# SimpleC64-128Cart-Dual.net
KiCad netlist of a schematic drawn in EAGLE
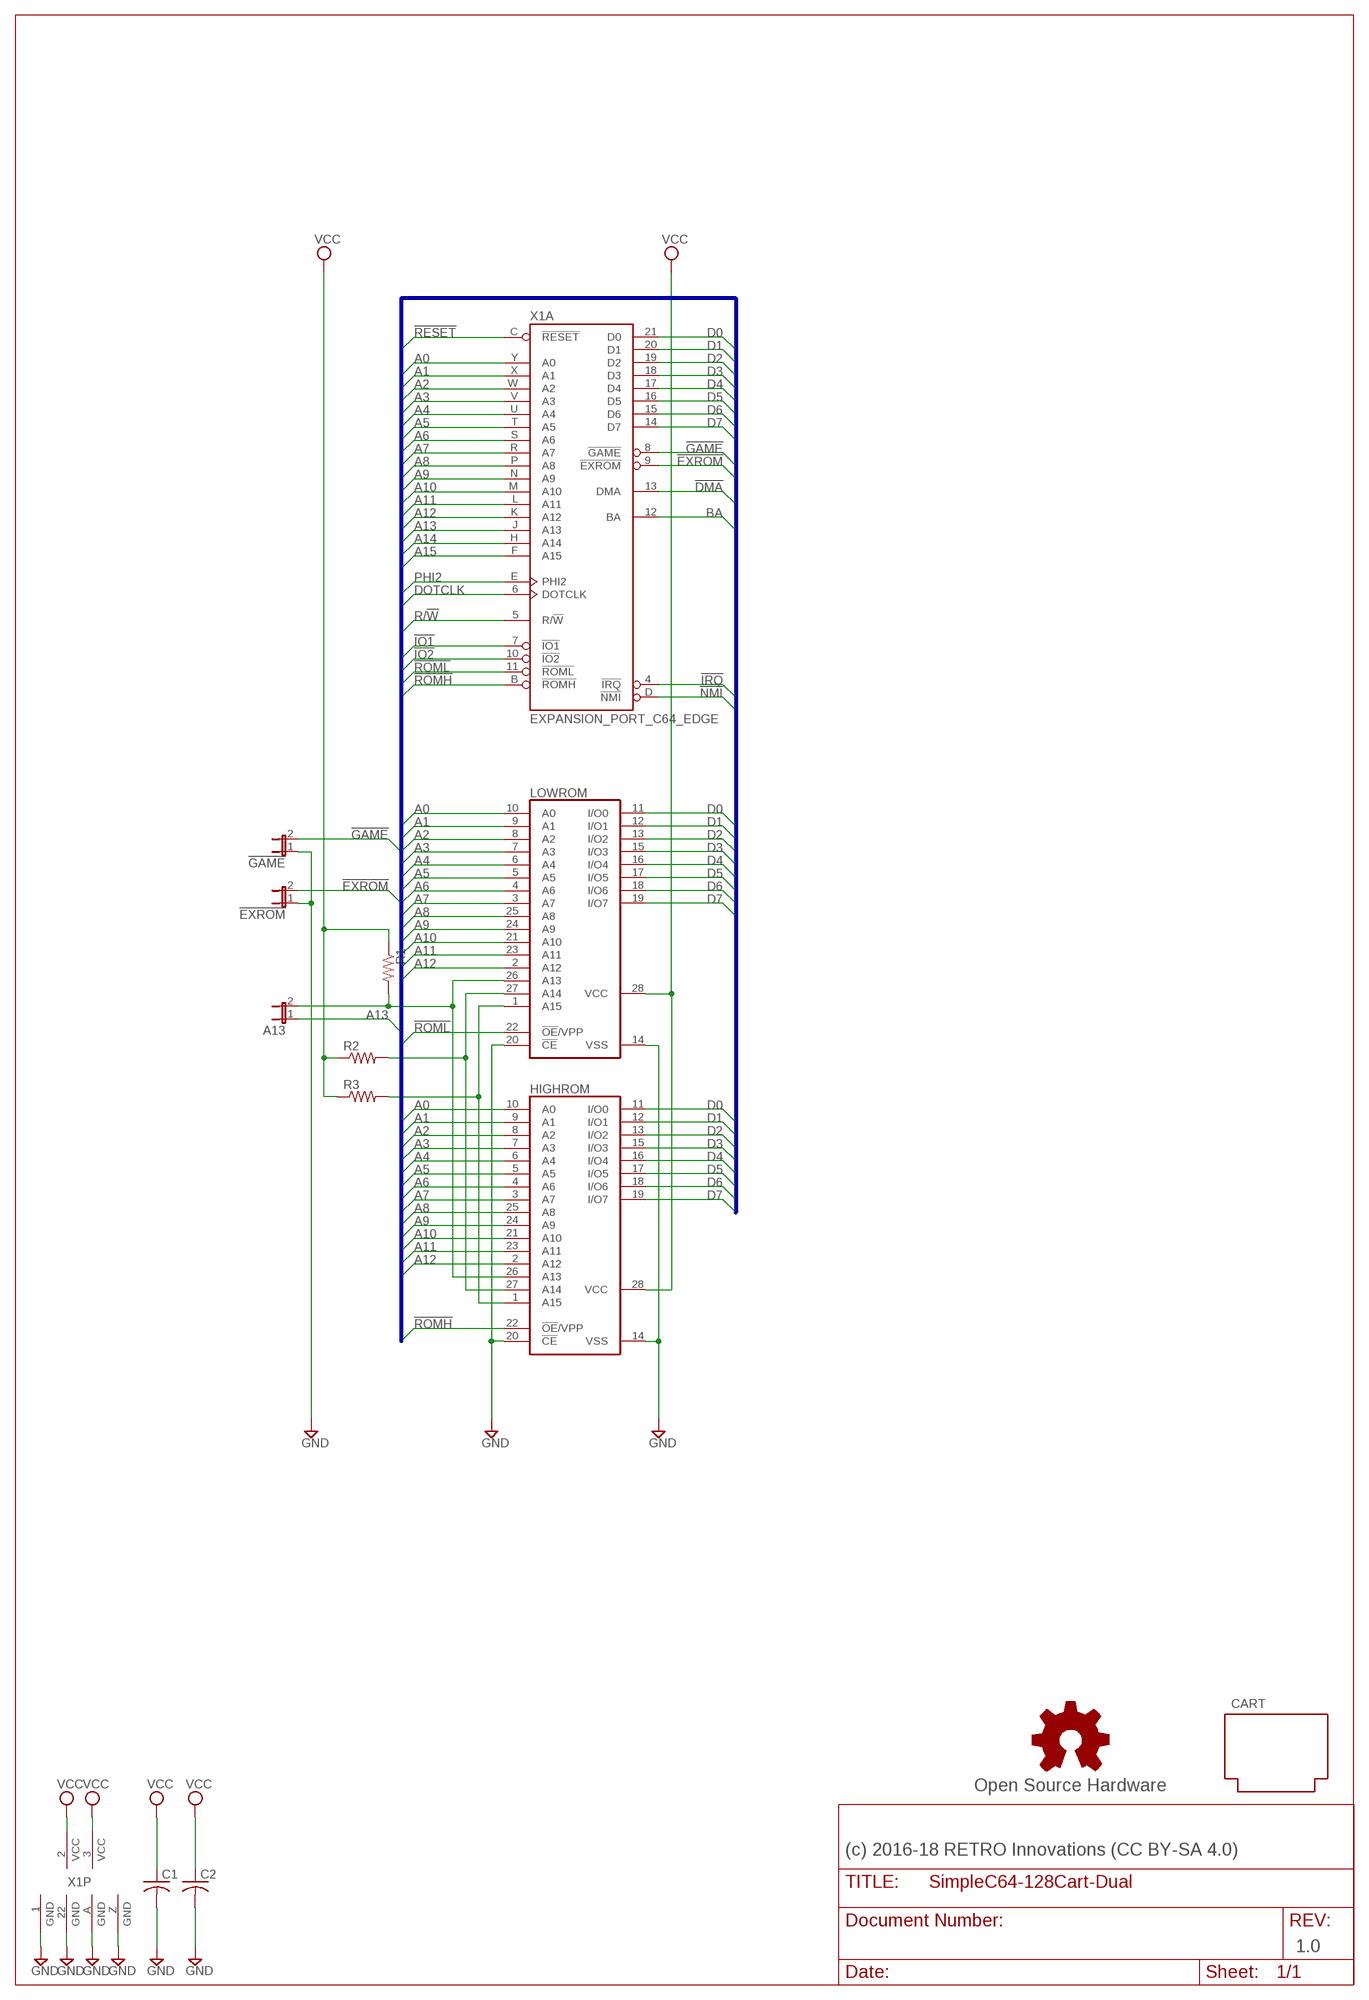
[diagram p0: schematic, sheet 1]

(export (version "E")
  (design (tool "Eeschema 10.0.6"))
  (components
    (comp (ref "!EXROM")
      (value "JP1E")
      (footprint "eagle-import:JP1")
      (libsource (lib "eagle-import") (part "JP1E"))
    )
    (comp (ref "!GAME")
      (value "JP1E")
      (footprint "eagle-import:JP1")
      (libsource (lib "eagle-import") (part "JP1E"))
    )
    (comp (ref "A13")
      (value "JP1E")
      (footprint "eagle-import:JP1")
      (libsource (lib "eagle-import") (part "JP1E"))
    )
    (comp (ref "C1")
      (value "C-US025-025X050")
      (footprint "eagle-import:C025-025X050")
      (libsource (lib "eagle-import") (part "C-US025-025X050"))
    )
    (comp (ref "C2")
      (value "C-US025-025X050")
      (footprint "eagle-import:C025-025X050")
      (libsource (lib "eagle-import") (part "C-US025-025X050"))
    )
    (comp (ref "CART")
      (value "CARTRIDGE_C64")
      (footprint "eagle-import:CARTRIDGE_C64")
      (libsource (lib "eagle-import") (part "CARTRIDGE_C64"))
    )
    (comp (ref "GOLD_ORB_SM1")
      (value "Open Source Hardware")
      (footprint "eagle-import:OSHW_8MM")
      (libsource (lib "eagle-import") (part "OSHWLOGOLOGO8MM"))
    )
    (comp (ref "HIGHROM")
      (value "27512G")
      (footprint "eagle-import:DIL28-6")
      (libsource (lib "eagle-import") (part "27512G"))
    )
    (comp (ref "LOWROM")
      (value "27512G")
      (footprint "eagle-import:DIL28-6")
      (libsource (lib "eagle-import") (part "27512G"))
    )
    (comp (ref "R1")
      (value "R-US_0204/7")
      (footprint "eagle-import:0204_7")
      (libsource (lib "eagle-import") (part "R-US_0204/7"))
    )
    (comp (ref "R2")
      (value "R-US_0204/7")
      (footprint "eagle-import:0204_7")
      (libsource (lib "eagle-import") (part "R-US_0204/7"))
    )
    (comp (ref "R3")
      (value "R-US_0204/7")
      (footprint "eagle-import:0204_7")
      (libsource (lib "eagle-import") (part "R-US_0204/7"))
    )
    (comp (ref "X1")
      (value "EXPANSION_PORT_C64_EDGE")
      (footprint "eagle-import:MA100-22-2")
      (libsource (lib "eagle-import") (part "EXPANSION_PORT_C64_EDGE"))
    )
  )
  (nets
    (net (code "1") (name "/A0") (class "Default")
      (node (ref "HIGHROM") (pin "10") (pinfunction "A0_10") (pintype "input"))
      (node (ref "LOWROM") (pin "10") (pinfunction "A0_10") (pintype "input"))
      (node (ref "X1") (pin "Y") (pinfunction "A0_Y") (pintype "bidirectional"))
    )
    (net (code "2") (name "/A1") (class "Default")
      (node (ref "HIGHROM") (pin "9") (pinfunction "A1_9") (pintype "input"))
      (node (ref "LOWROM") (pin "9") (pinfunction "A1_9") (pintype "input"))
      (node (ref "X1") (pin "X") (pinfunction "A1_X") (pintype "bidirectional"))
    )
    (net (code "3") (name "/A2") (class "Default")
      (node (ref "HIGHROM") (pin "8") (pinfunction "A2_8") (pintype "input"))
      (node (ref "LOWROM") (pin "8") (pinfunction "A2_8") (pintype "input"))
      (node (ref "X1") (pin "W") (pinfunction "A2_W") (pintype "bidirectional"))
    )
    (net (code "4") (name "/A3") (class "Default")
      (node (ref "HIGHROM") (pin "7") (pinfunction "A3_7") (pintype "input"))
      (node (ref "LOWROM") (pin "7") (pinfunction "A3_7") (pintype "input"))
      (node (ref "X1") (pin "V") (pinfunction "A3_V") (pintype "bidirectional"))
    )
    (net (code "5") (name "/A4") (class "Default")
      (node (ref "HIGHROM") (pin "6") (pinfunction "A4_6") (pintype "input"))
      (node (ref "LOWROM") (pin "6") (pinfunction "A4_6") (pintype "input"))
      (node (ref "X1") (pin "U") (pinfunction "A4_U") (pintype "bidirectional"))
    )
    (net (code "6") (name "/A5") (class "Default")
      (node (ref "HIGHROM") (pin "5") (pinfunction "A5_5") (pintype "input"))
      (node (ref "LOWROM") (pin "5") (pinfunction "A5_5") (pintype "input"))
      (node (ref "X1") (pin "T") (pinfunction "A5_T") (pintype "bidirectional"))
    )
    (net (code "7") (name "/A6") (class "Default")
      (node (ref "HIGHROM") (pin "4") (pinfunction "A6_4") (pintype "input"))
      (node (ref "LOWROM") (pin "4") (pinfunction "A6_4") (pintype "input"))
      (node (ref "X1") (pin "S") (pinfunction "A6_S") (pintype "bidirectional"))
    )
    (net (code "8") (name "/A7") (class "Default")
      (node (ref "HIGHROM") (pin "3") (pinfunction "A7_3") (pintype "input"))
      (node (ref "LOWROM") (pin "3") (pinfunction "A7_3") (pintype "input"))
      (node (ref "X1") (pin "R") (pinfunction "A7_R") (pintype "bidirectional"))
    )
    (net (code "9") (name "/A8") (class "Default")
      (node (ref "HIGHROM") (pin "25") (pinfunction "A8_25") (pintype "input"))
      (node (ref "LOWROM") (pin "25") (pinfunction "A8_25") (pintype "input"))
      (node (ref "X1") (pin "P") (pinfunction "A8_P") (pintype "bidirectional"))
    )
    (net (code "10") (name "/A9") (class "Default")
      (node (ref "HIGHROM") (pin "24") (pinfunction "A9_24") (pintype "input"))
      (node (ref "LOWROM") (pin "24") (pinfunction "A9_24") (pintype "input"))
      (node (ref "X1") (pin "N") (pinfunction "A9_N") (pintype "bidirectional"))
    )
    (net (code "11") (name "/A10") (class "Default")
      (node (ref "HIGHROM") (pin "21") (pinfunction "A10_21") (pintype "input"))
      (node (ref "LOWROM") (pin "21") (pinfunction "A10_21") (pintype "input"))
      (node (ref "X1") (pin "M") (pinfunction "A10_M") (pintype "bidirectional"))
    )
    (net (code "12") (name "/A11") (class "Default")
      (node (ref "HIGHROM") (pin "23") (pinfunction "A11_23") (pintype "input"))
      (node (ref "LOWROM") (pin "23") (pinfunction "A11_23") (pintype "input"))
      (node (ref "X1") (pin "L") (pinfunction "A11_L") (pintype "bidirectional"))
    )
    (net (code "13") (name "/A12") (class "Default")
      (node (ref "HIGHROM") (pin "2") (pinfunction "A12_2") (pintype "input"))
      (node (ref "LOWROM") (pin "2") (pinfunction "A12_2") (pintype "input"))
      (node (ref "X1") (pin "K") (pinfunction "A12_K") (pintype "bidirectional"))
    )
    (net (code "14") (name "/A13") (class "Default")
      (node (ref "A13") (pin "1") (pinfunction "1_1") (pintype "passive"))
      (node (ref "X1") (pin "J") (pinfunction "A13_J") (pintype "bidirectional"))
    )
    (net (code "15") (name "/A14") (class "Default")
      (node (ref "X1") (pin "H") (pinfunction "A14_H") (pintype "bidirectional"))
    )
    (net (code "16") (name "/A15") (class "Default")
      (node (ref "X1") (pin "F") (pinfunction "A15_F") (pintype "bidirectional"))
    )
    (net (code "17") (name "/BA") (class "Default")
      (node (ref "X1") (pin "12") (pinfunction "BA_12") (pintype "bidirectional"))
    )
    (net (code "18") (name "/D0") (class "Default")
      (node (ref "HIGHROM") (pin "11") (pinfunction "I/O0_11") (pintype "tri_state"))
      (node (ref "LOWROM") (pin "11") (pinfunction "I/O0_11") (pintype "tri_state"))
      (node (ref "X1") (pin "21") (pinfunction "D0_21") (pintype "bidirectional"))
    )
    (net (code "19") (name "/D1") (class "Default")
      (node (ref "HIGHROM") (pin "12") (pinfunction "I/O1_12") (pintype "tri_state"))
      (node (ref "LOWROM") (pin "12") (pinfunction "I/O1_12") (pintype "tri_state"))
      (node (ref "X1") (pin "20") (pinfunction "D1_20") (pintype "bidirectional"))
    )
    (net (code "20") (name "/D2") (class "Default")
      (node (ref "HIGHROM") (pin "13") (pinfunction "I/O2_13") (pintype "tri_state"))
      (node (ref "LOWROM") (pin "13") (pinfunction "I/O2_13") (pintype "tri_state"))
      (node (ref "X1") (pin "19") (pinfunction "D2_19") (pintype "bidirectional"))
    )
    (net (code "21") (name "/D3") (class "Default")
      (node (ref "HIGHROM") (pin "15") (pinfunction "I/O3_15") (pintype "tri_state"))
      (node (ref "LOWROM") (pin "15") (pinfunction "I/O3_15") (pintype "tri_state"))
      (node (ref "X1") (pin "18") (pinfunction "D3_18") (pintype "bidirectional"))
    )
    (net (code "22") (name "/D4") (class "Default")
      (node (ref "HIGHROM") (pin "16") (pinfunction "I/O4_16") (pintype "tri_state"))
      (node (ref "LOWROM") (pin "16") (pinfunction "I/O4_16") (pintype "tri_state"))
      (node (ref "X1") (pin "17") (pinfunction "D4_17") (pintype "bidirectional"))
    )
    (net (code "23") (name "/D5") (class "Default")
      (node (ref "HIGHROM") (pin "17") (pinfunction "I/O5_17") (pintype "tri_state"))
      (node (ref "LOWROM") (pin "17") (pinfunction "I/O5_17") (pintype "tri_state"))
      (node (ref "X1") (pin "16") (pinfunction "D5_16") (pintype "bidirectional"))
    )
    (net (code "24") (name "/D6") (class "Default")
      (node (ref "HIGHROM") (pin "18") (pinfunction "I/O6_18") (pintype "tri_state"))
      (node (ref "LOWROM") (pin "18") (pinfunction "I/O6_18") (pintype "tri_state"))
      (node (ref "X1") (pin "15") (pinfunction "D6_15") (pintype "bidirectional"))
    )
    (net (code "25") (name "/D7") (class "Default")
      (node (ref "HIGHROM") (pin "19") (pinfunction "I/O7_19") (pintype "tri_state"))
      (node (ref "LOWROM") (pin "19") (pinfunction "I/O7_19") (pintype "tri_state"))
      (node (ref "X1") (pin "14") (pinfunction "D7_14") (pintype "bidirectional"))
    )
    (net (code "26") (name "/DOTCLK") (class "Default")
      (node (ref "X1") (pin "6") (pinfunction "DOTCLK_6") (pintype "output"))
    )
    (net (code "27") (name "/PHI2") (class "Default")
      (node (ref "X1") (pin "E") (pinfunction "PHI2_E") (pintype "output"))
    )
    (net (code "28") (name "/R{slash}~{W}") (class "Default")
      (node (ref "X1") (pin "5") (pinfunction "R/~{W}_5") (pintype "bidirectional"))
    )
    (net (code "29") (name "/~{DMA}") (class "Default")
      (node (ref "X1") (pin "13") (pinfunction "DMA_13") (pintype "bidirectional"))
    )
    (net (code "30") (name "/~{EXROM}") (class "Default")
      (node (ref "!EXROM") (pin "2") (pinfunction "2_2") (pintype "passive"))
      (node (ref "X1") (pin "9") (pinfunction "~{EXROM}_9") (pintype "input"))
    )
    (net (code "31") (name "/~{GAME}") (class "Default")
      (node (ref "!GAME") (pin "2") (pinfunction "2_2") (pintype "passive"))
      (node (ref "X1") (pin "8") (pinfunction "~{GAME}_8") (pintype "input"))
    )
    (net (code "32") (name "/~{IO1}") (class "Default")
      (node (ref "X1") (pin "7") (pinfunction "~{IO1}_7") (pintype "output"))
    )
    (net (code "33") (name "/~{IO2}") (class "Default")
      (node (ref "X1") (pin "10") (pinfunction "~{IO2}_10") (pintype "output"))
    )
    (net (code "34") (name "/~{IRQ}") (class "Default")
      (node (ref "X1") (pin "4") (pinfunction "~{IRQ}_4") (pintype "open_collector"))
    )
    (net (code "35") (name "/~{NMI}") (class "Default")
      (node (ref "X1") (pin "D") (pinfunction "~{NMI}_D") (pintype "open_collector"))
    )
    (net (code "36") (name "/~{RESET}") (class "Default")
      (node (ref "X1") (pin "C") (pinfunction "~{RESET}_C") (pintype "open_collector"))
    )
    (net (code "37") (name "/~{ROMH}") (class "Default")
      (node (ref "HIGHROM") (pin "22") (pinfunction "~{OE}/VPP_22") (pintype "input"))
      (node (ref "X1") (pin "B") (pinfunction "~{ROMH}_B") (pintype "output"))
    )
    (net (code "38") (name "/~{ROML}") (class "Default")
      (node (ref "LOWROM") (pin "22") (pinfunction "~{OE}/VPP_22") (pintype "input"))
      (node (ref "X1") (pin "11") (pinfunction "~{ROML}_11") (pintype "output"))
    )
    (net (code "39") (name "GND") (class "Default")
      (node (ref "!EXROM") (pin "1") (pinfunction "1_1") (pintype "passive"))
      (node (ref "!GAME") (pin "1") (pinfunction "1_1") (pintype "passive"))
      (node (ref "C1") (pin "2") (pinfunction "2_2") (pintype "passive"))
      (node (ref "C2") (pin "2") (pinfunction "2_2") (pintype "passive"))
      (node (ref "HIGHROM") (pin "14") (pinfunction "VSS_14") (pintype "power_in"))
      (node (ref "HIGHROM") (pin "20") (pinfunction "~{CE}_20") (pintype "input"))
      (node (ref "LOWROM") (pin "14") (pinfunction "VSS_14") (pintype "power_in"))
      (node (ref "LOWROM") (pin "20") (pinfunction "~{CE}_20") (pintype "input"))
      (node (ref "X1") (pin "1") (pinfunction "GND_1") (pintype "power_in"))
      (node (ref "X1") (pin "22") (pinfunction "GND_22") (pintype "power_in"))
      (node (ref "X1") (pin "A") (pinfunction "GND_A") (pintype "power_in"))
      (node (ref "X1") (pin "Z") (pinfunction "GND_Z") (pintype "power_in"))
    )
    (net (code "40") (name "Net-(HIGHROM-A13)") (class "Default")
      (node (ref "A13") (pin "2") (pinfunction "2_2") (pintype "passive"))
      (node (ref "HIGHROM") (pin "26") (pinfunction "A13_26") (pintype "input"))
      (node (ref "LOWROM") (pin "26") (pinfunction "A13_26") (pintype "input"))
      (node (ref "R1") (pin "2") (pinfunction "2_2") (pintype "passive"))
    )
    (net (code "41") (name "Net-(HIGHROM-A14)") (class "Default")
      (node (ref "HIGHROM") (pin "27") (pinfunction "A14_27") (pintype "input"))
      (node (ref "LOWROM") (pin "27") (pinfunction "A14_27") (pintype "input"))
      (node (ref "R2") (pin "2") (pinfunction "2_2") (pintype "passive"))
    )
    (net (code "42") (name "Net-(HIGHROM-A15)") (class "Default")
      (node (ref "HIGHROM") (pin "1") (pinfunction "A15_1") (pintype "input"))
      (node (ref "LOWROM") (pin "1") (pinfunction "A15_1") (pintype "input"))
      (node (ref "R3") (pin "2") (pinfunction "2_2") (pintype "passive"))
    )
    (net (code "43") (name "VCC") (class "Default")
      (node (ref "C1") (pin "1") (pinfunction "1_1") (pintype "passive"))
      (node (ref "C2") (pin "1") (pinfunction "1_1") (pintype "passive"))
      (node (ref "HIGHROM") (pin "28") (pinfunction "VCC_28") (pintype "power_in"))
      (node (ref "LOWROM") (pin "28") (pinfunction "VCC_28") (pintype "power_in"))
      (node (ref "R1") (pin "1") (pinfunction "1_1") (pintype "passive"))
      (node (ref "R2") (pin "1") (pinfunction "1_1") (pintype "passive"))
      (node (ref "R3") (pin "1") (pinfunction "1_1") (pintype "passive"))
      (node (ref "X1") (pin "2") (pinfunction "VCC_2") (pintype "power_in"))
      (node (ref "X1") (pin "3") (pinfunction "VCC_3") (pintype "power_in"))
    )
  )
)
